# Celestron_Telescope_GPSRX-BT-WiFi-1_09.net
KiCad netlist of a schematic drawn in EAGLE
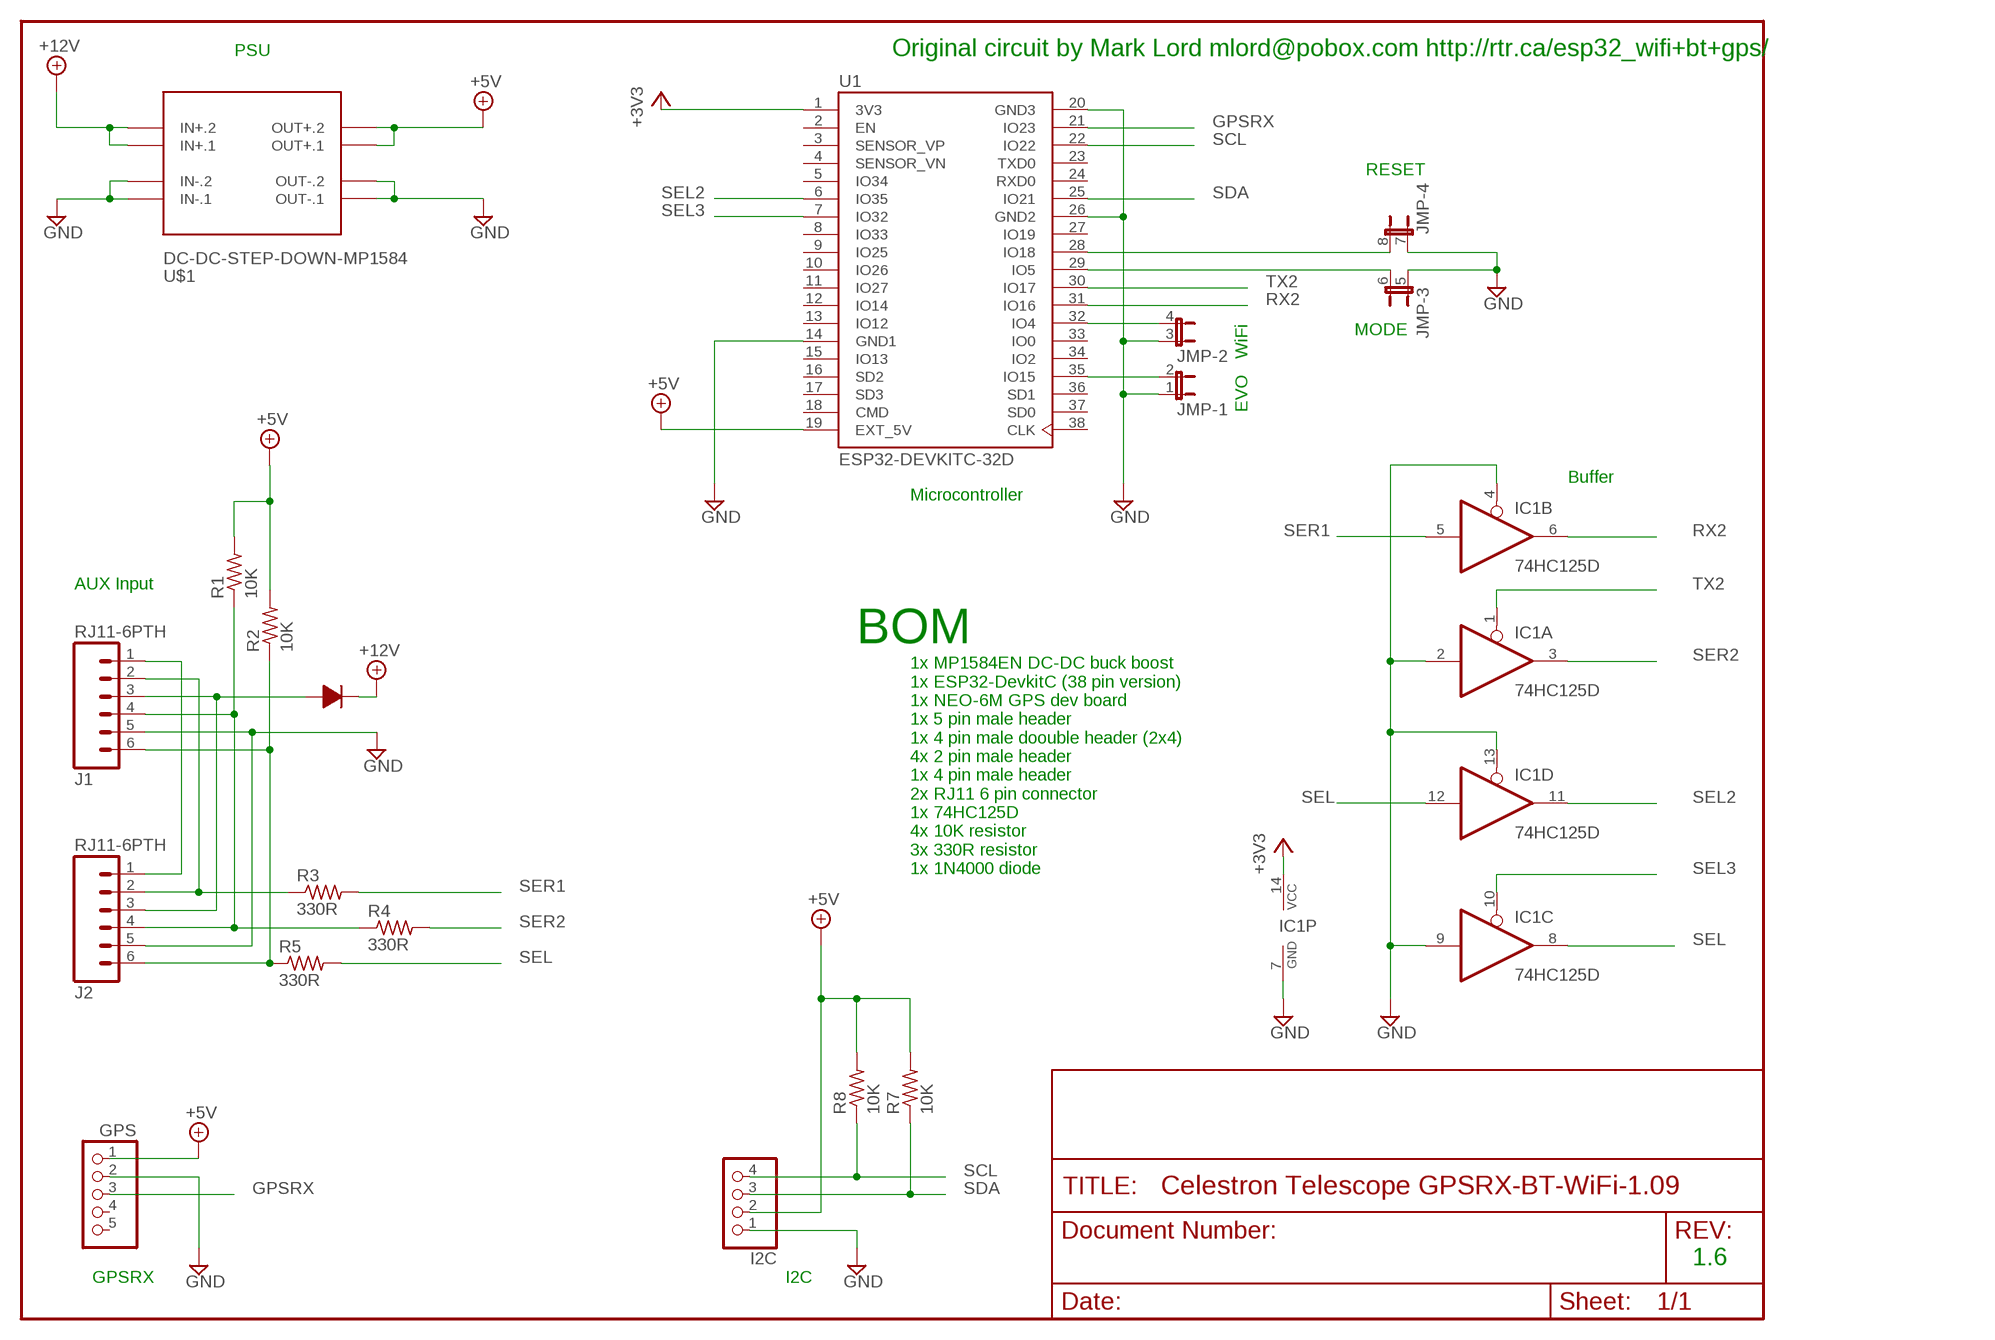
[diagram p0: schematic, sheet 1]

(export (version "E")
  (design (tool "Eeschema 10.0.6"))
  (components
    (comp (ref "GPS")
      (value "PINHD-1X5")
      (footprint "eagle-import:1X05")
      (libsource (lib "eagle-import") (part "PINHD-1X5"))
    )
    (comp (ref "I2C")
      (value "PINHD-1X4")
      (footprint "eagle-import:1X04")
      (libsource (lib "eagle-import") (part "PINHD-1X4"))
    )
    (comp (ref "IC1")
      (value "74HC125D")
      (footprint "eagle-import:SO14")
      (libsource (lib "eagle-import") (part "74125DHC"))
    )
    (comp (ref "J1")
      (value "RJ11-6PTH")
      (footprint "eagle-import:RJ11-6")
      (libsource (lib "eagle-import") (part "RJ11-6PTH"))
    )
    (comp (ref "J2")
      (value "RJ11-6PTH")
      (footprint "eagle-import:RJ11-6")
      (libsource (lib "eagle-import") (part "RJ11-6PTH"))
    )
    (comp (ref "JMP")
      (value "JP4QE")
      (footprint "eagle-import:JP4Q")
      (libsource (lib "eagle-import") (part "JP4QE"))
    )
    (comp (ref "R1")
      (value "10K")
      (footprint "eagle-import:M0805")
      (libsource (lib "eagle-import") (part "R-US_M0805"))
    )
    (comp (ref "R2")
      (value "10K")
      (footprint "eagle-import:M0805")
      (libsource (lib "eagle-import") (part "R-US_M0805"))
    )
    (comp (ref "R3")
      (value "330R")
      (footprint "eagle-import:M0805")
      (libsource (lib "eagle-import") (part "R-US_M0805"))
    )
    (comp (ref "R4")
      (value "330R")
      (footprint "eagle-import:M0805")
      (libsource (lib "eagle-import") (part "R-US_M0805"))
    )
    (comp (ref "R5")
      (value "330R")
      (footprint "eagle-import:M0805")
      (libsource (lib "eagle-import") (part "R-US_M0805"))
    )
    (comp (ref "R7")
      (value "10K")
      (footprint "eagle-import:M0805")
      (libsource (lib "eagle-import") (part "R-US_M0805"))
    )
    (comp (ref "R8")
      (value "10K")
      (footprint "eagle-import:M0805")
      (libsource (lib "eagle-import") (part "R-US_M0805"))
    )
    (comp (ref "U$1")
      (value "DC-DC-STEP-DOWN-MP1584")
      (footprint "eagle-import:DC-DC-STEP-DOWN-MP1584")
      (libsource (lib "eagle-import") (part "DC-DC-STEP-DOWN-MP1584"))
    )
    (comp (ref "U$2")
      (value "1N4001")
      (footprint "eagle-import:DIODE-12.70")
      (libsource (lib "eagle-import") (part "1N4001"))
    )
    (comp (ref "U1")
      (value "ESP32-DEVKITC-32D")
      (footprint "eagle-import:MODULE_ESP32-DEVKITC-32D")
      (fields (field (name "MF") "Espressif Systems"))
      (libsource (lib "eagle-import") (part "ESP32-DEVKITC-32D"))
    )
  )
  (nets
    (net (code "1") (name "+3V3") (class "Default")
      (node (ref "IC1") (pin "14") (pinfunction "VCC_14") (pintype "power_in"))
      (node (ref "U1") (pin "1") (pinfunction "3V3_1") (pintype "power_in"))
    )
    (net (code "2") (name "+5V") (class "Default")
      (node (ref "GPS") (pin "1") (pinfunction "1_1") (pintype "passive"))
      (node (ref "I2C") (pin "2") (pinfunction "2_2") (pintype "passive"))
      (node (ref "R1") (pin "2") (pinfunction "2_2") (pintype "passive"))
      (node (ref "R2") (pin "2") (pinfunction "2_2") (pintype "passive"))
      (node (ref "R7") (pin "2") (pinfunction "2_2") (pintype "passive"))
      (node (ref "R8") (pin "2") (pinfunction "2_2") (pintype "passive"))
      (node (ref "U$1") (pin "OUT+.1") (pinfunction "OUT+.1_OUT+.1") (pintype "bidirectional"))
      (node (ref "U$1") (pin "OUT+.2") (pinfunction "OUT+.2_OUT+.2") (pintype "bidirectional"))
      (node (ref "U1") (pin "19") (pinfunction "EXT_5V_19") (pintype "power_in"))
    )
    (net (code "3") (name "+12V") (class "Default")
      (node (ref "U$1") (pin "IN+.1") (pinfunction "IN+.1_IN+.1") (pintype "bidirectional"))
      (node (ref "U$1") (pin "IN+.2") (pinfunction "IN+.2_IN+.2") (pintype "bidirectional"))
      (node (ref "U$2") (pin "P$2") (pinfunction "P$2_P$2") (pintype "passive"))
    )
    (net (code "4") (name "/GPSRX") (class "Default")
      (node (ref "GPS") (pin "3") (pinfunction "3_3") (pintype "passive"))
      (node (ref "U1") (pin "21") (pinfunction "IO23_21") (pintype "bidirectional"))
    )
    (net (code "5") (name "/RX2") (class "Default")
      (node (ref "IC1") (pin "6") (pinfunction "O_6") (pintype "tri_state"))
      (node (ref "U1") (pin "31") (pinfunction "IO16_31") (pintype "bidirectional"))
    )
    (net (code "6") (name "/SCL") (class "Default")
      (node (ref "I2C") (pin "4") (pinfunction "4_4") (pintype "passive"))
      (node (ref "R8") (pin "1") (pinfunction "1_1") (pintype "passive"))
      (node (ref "U1") (pin "22") (pinfunction "IO22_22") (pintype "bidirectional"))
    )
    (net (code "7") (name "/SDA") (class "Default")
      (node (ref "I2C") (pin "3") (pinfunction "3_3") (pintype "passive"))
      (node (ref "R7") (pin "1") (pinfunction "1_1") (pintype "passive"))
      (node (ref "U1") (pin "25") (pinfunction "IO21_25") (pintype "bidirectional"))
    )
    (net (code "8") (name "/SEL") (class "Default")
      (node (ref "IC1") (pin "12") (pinfunction "I_12") (pintype "input"))
      (node (ref "IC1") (pin "8") (pinfunction "O_8") (pintype "tri_state"))
      (node (ref "R5") (pin "2") (pinfunction "2_2") (pintype "passive"))
    )
    (net (code "9") (name "/SEL2") (class "Default")
      (node (ref "IC1") (pin "11") (pinfunction "O_11") (pintype "tri_state"))
      (node (ref "U1") (pin "6") (pinfunction "IO35_6") (pintype "bidirectional"))
    )
    (net (code "10") (name "/SEL3") (class "Default")
      (node (ref "IC1") (pin "10") (pinfunction "OE_10") (pintype "input"))
      (node (ref "U1") (pin "7") (pinfunction "IO32_7") (pintype "bidirectional"))
    )
    (net (code "11") (name "/SER1") (class "Default")
      (node (ref "IC1") (pin "5") (pinfunction "I_5") (pintype "input"))
      (node (ref "R3") (pin "2") (pinfunction "2_2") (pintype "passive"))
    )
    (net (code "12") (name "/SER2") (class "Default")
      (node (ref "IC1") (pin "3") (pinfunction "O_3") (pintype "tri_state"))
      (node (ref "R4") (pin "2") (pinfunction "2_2") (pintype "passive"))
    )
    (net (code "13") (name "/TX2") (class "Default")
      (node (ref "IC1") (pin "1") (pinfunction "OE_1") (pintype "input"))
      (node (ref "U1") (pin "30") (pinfunction "IO17_30") (pintype "bidirectional"))
    )
    (net (code "14") (name "GND") (class "Default")
      (node (ref "GPS") (pin "2") (pinfunction "2_2") (pintype "passive"))
      (node (ref "I2C") (pin "1") (pinfunction "1_1") (pintype "passive"))
      (node (ref "IC1") (pin "13") (pinfunction "OE_13") (pintype "input"))
      (node (ref "IC1") (pin "2") (pinfunction "I_2") (pintype "input"))
      (node (ref "IC1") (pin "4") (pinfunction "OE_4") (pintype "input"))
      (node (ref "IC1") (pin "7") (pinfunction "GND_7") (pintype "power_in"))
      (node (ref "IC1") (pin "9") (pinfunction "I_9") (pintype "input"))
      (node (ref "J1") (pin "5") (pinfunction "5_5") (pintype "passive"))
      (node (ref "J2") (pin "5") (pinfunction "5_5") (pintype "passive"))
      (node (ref "JMP") (pin "1") (pinfunction "1_1") (pintype "passive"))
      (node (ref "JMP") (pin "3") (pinfunction "1_3") (pintype "passive"))
      (node (ref "JMP") (pin "5") (pinfunction "1_5") (pintype "passive"))
      (node (ref "JMP") (pin "7") (pinfunction "1_7") (pintype "passive"))
      (node (ref "U$1") (pin "IN-.1") (pinfunction "IN-.1_IN-.1") (pintype "bidirectional"))
      (node (ref "U$1") (pin "IN-.2") (pinfunction "IN-.2_IN-.2") (pintype "bidirectional"))
      (node (ref "U$1") (pin "OUT-.1") (pinfunction "OUT-.1_OUT-.1") (pintype "bidirectional"))
      (node (ref "U$1") (pin "OUT-.2") (pinfunction "OUT-.2_OUT-.2") (pintype "bidirectional"))
      (node (ref "U1") (pin "14") (pinfunction "GND1_14") (pintype "power_in"))
      (node (ref "U1") (pin "20") (pinfunction "GND3_20") (pintype "power_in"))
      (node (ref "U1") (pin "26") (pinfunction "GND2_26") (pintype "power_in"))
    )
    (net (code "15") (name "Net-(J1-Pad1)") (class "Default")
      (node (ref "J1") (pin "1") (pinfunction "1_1") (pintype "passive"))
      (node (ref "J2") (pin "1") (pinfunction "1_1") (pintype "passive"))
    )
    (net (code "16") (name "Net-(J1-Pad2)") (class "Default")
      (node (ref "J1") (pin "2") (pinfunction "2_2") (pintype "passive"))
      (node (ref "J2") (pin "2") (pinfunction "2_2") (pintype "passive"))
      (node (ref "R3") (pin "1") (pinfunction "1_1") (pintype "passive"))
    )
    (net (code "17") (name "Net-(J1-Pad3)") (class "Default")
      (node (ref "J1") (pin "3") (pinfunction "3_3") (pintype "passive"))
      (node (ref "J2") (pin "3") (pinfunction "3_3") (pintype "passive"))
      (node (ref "U$2") (pin "P$1") (pinfunction "P$1_P$1") (pintype "passive"))
    )
    (net (code "18") (name "Net-(J1-Pad4)") (class "Default")
      (node (ref "J1") (pin "4") (pinfunction "4_4") (pintype "passive"))
      (node (ref "J2") (pin "4") (pinfunction "4_4") (pintype "passive"))
      (node (ref "R1") (pin "1") (pinfunction "1_1") (pintype "passive"))
      (node (ref "R4") (pin "1") (pinfunction "1_1") (pintype "passive"))
    )
    (net (code "19") (name "Net-(J1-Pad6)") (class "Default")
      (node (ref "J1") (pin "6") (pinfunction "6_6") (pintype "passive"))
      (node (ref "J2") (pin "6") (pinfunction "6_6") (pintype "passive"))
      (node (ref "R2") (pin "1") (pinfunction "1_1") (pintype "passive"))
      (node (ref "R5") (pin "1") (pinfunction "1_1") (pintype "passive"))
    )
    (net (code "20") (name "Net-(JMPB-2)") (class "Default")
      (node (ref "JMP") (pin "4") (pinfunction "2_4") (pintype "passive"))
      (node (ref "U1") (pin "32") (pinfunction "IO4_32") (pintype "bidirectional"))
    )
    (net (code "21") (name "Net-(JMPC-2)") (class "Default")
      (node (ref "JMP") (pin "6") (pinfunction "2_6") (pintype "passive"))
      (node (ref "U1") (pin "29") (pinfunction "IO5_29") (pintype "bidirectional"))
    )
    (net (code "22") (name "Net-(JMPD-2)") (class "Default")
      (node (ref "JMP") (pin "8") (pinfunction "2_8") (pintype "passive"))
      (node (ref "U1") (pin "28") (pinfunction "IO18_28") (pintype "bidirectional"))
    )
    (net (code "23") (name "Net-(U1-IO15)") (class "Default")
      (node (ref "JMP") (pin "2") (pinfunction "2_2") (pintype "passive"))
      (node (ref "U1") (pin "35") (pinfunction "IO15_35") (pintype "bidirectional"))
    )
    (net (code "24") (name "unconnected-(GPS-Pad4)") (class "Default")
      (node (ref "GPS") (pin "4") (pinfunction "4_4") (pintype "passive"))
    )
    (net (code "25") (name "unconnected-(GPS-Pad5)") (class "Default")
      (node (ref "GPS") (pin "5") (pinfunction "5_5") (pintype "passive"))
    )
    (net (code "26") (name "unconnected-(U1-CLK-Pad38)") (class "Default")
      (node (ref "U1") (pin "38") (pinfunction "CLK_38") (pintype "input"))
    )
    (net (code "27") (name "unconnected-(U1-CMD-Pad18)") (class "Default")
      (node (ref "U1") (pin "18") (pinfunction "CMD_18") (pintype "bidirectional"))
    )
    (net (code "28") (name "unconnected-(U1-EN-Pad2)") (class "Default")
      (node (ref "U1") (pin "2") (pinfunction "EN_2") (pintype "input"))
    )
    (net (code "29") (name "unconnected-(U1-IO0-Pad33)") (class "Default")
      (node (ref "U1") (pin "33") (pinfunction "IO0_33") (pintype "bidirectional"))
    )
    (net (code "30") (name "unconnected-(U1-IO2-Pad34)") (class "Default")
      (node (ref "U1") (pin "34") (pinfunction "IO2_34") (pintype "bidirectional"))
    )
    (net (code "31") (name "unconnected-(U1-IO12-Pad13)") (class "Default")
      (node (ref "U1") (pin "13") (pinfunction "IO12_13") (pintype "bidirectional"))
    )
    (net (code "32") (name "unconnected-(U1-IO13-Pad15)") (class "Default")
      (node (ref "U1") (pin "15") (pinfunction "IO13_15") (pintype "bidirectional"))
    )
    (net (code "33") (name "unconnected-(U1-IO14-Pad12)") (class "Default")
      (node (ref "U1") (pin "12") (pinfunction "IO14_12") (pintype "bidirectional"))
    )
    (net (code "34") (name "unconnected-(U1-IO19-Pad27)") (class "Default")
      (node (ref "U1") (pin "27") (pinfunction "IO19_27") (pintype "bidirectional"))
    )
    (net (code "35") (name "unconnected-(U1-IO25-Pad9)") (class "Default")
      (node (ref "U1") (pin "9") (pinfunction "IO25_9") (pintype "bidirectional"))
    )
    (net (code "36") (name "unconnected-(U1-IO26-Pad10)") (class "Default")
      (node (ref "U1") (pin "10") (pinfunction "IO26_10") (pintype "bidirectional"))
    )
    (net (code "37") (name "unconnected-(U1-IO27-Pad11)") (class "Default")
      (node (ref "U1") (pin "11") (pinfunction "IO27_11") (pintype "bidirectional"))
    )
    (net (code "38") (name "unconnected-(U1-IO33-Pad8)") (class "Default")
      (node (ref "U1") (pin "8") (pinfunction "IO33_8") (pintype "bidirectional"))
    )
    (net (code "39") (name "unconnected-(U1-IO34-Pad5)") (class "Default")
      (node (ref "U1") (pin "5") (pinfunction "IO34_5") (pintype "bidirectional"))
    )
    (net (code "40") (name "unconnected-(U1-RXD0-Pad24)") (class "Default")
      (node (ref "U1") (pin "24") (pinfunction "RXD0_24") (pintype "input"))
    )
    (net (code "41") (name "unconnected-(U1-SD0-Pad37)") (class "Default")
      (node (ref "U1") (pin "37") (pinfunction "SD0_37") (pintype "bidirectional"))
    )
    (net (code "42") (name "unconnected-(U1-SD1-Pad36)") (class "Default")
      (node (ref "U1") (pin "36") (pinfunction "SD1_36") (pintype "bidirectional"))
    )
    (net (code "43") (name "unconnected-(U1-SD2-Pad16)") (class "Default")
      (node (ref "U1") (pin "16") (pinfunction "SD2_16") (pintype "bidirectional"))
    )
    (net (code "44") (name "unconnected-(U1-SD3-Pad17)") (class "Default")
      (node (ref "U1") (pin "17") (pinfunction "SD3_17") (pintype "bidirectional"))
    )
    (net (code "45") (name "unconnected-(U1-SENSOR_VN-Pad4)") (class "Default")
      (node (ref "U1") (pin "4") (pinfunction "SENSOR_VN_4") (pintype "input"))
    )
    (net (code "46") (name "unconnected-(U1-SENSOR_VP-Pad3)") (class "Default")
      (node (ref "U1") (pin "3") (pinfunction "SENSOR_VP_3") (pintype "input"))
    )
    (net (code "47") (name "unconnected-(U1-TXD0-Pad23)") (class "Default")
      (node (ref "U1") (pin "23") (pinfunction "TXD0_23") (pintype "output"))
    )
  )
)
